# Volty.net
KiCad netlist of a schematic drawn in EAGLE
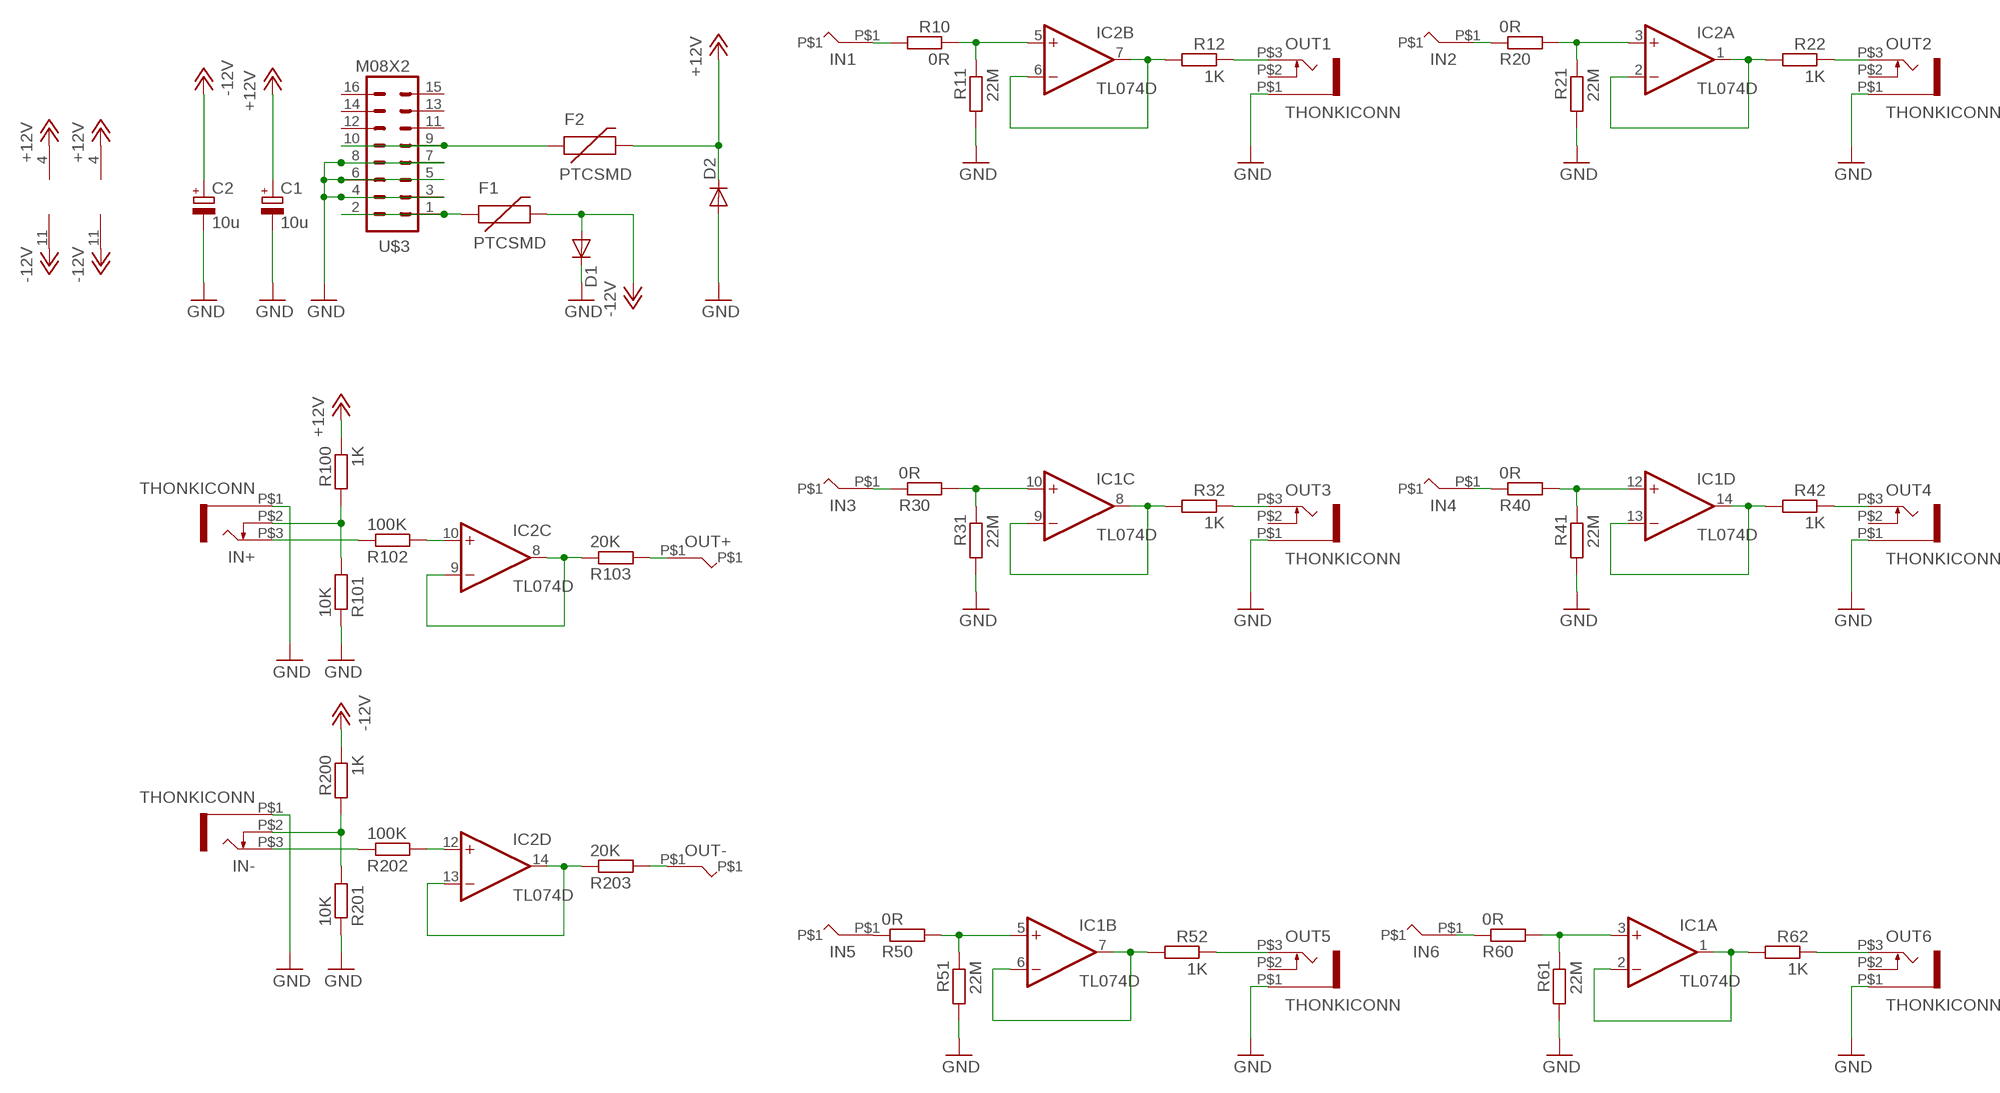
[diagram p0: schematic, sheet 1]

(export (version "E")
  (design (tool "Eeschema 10.0.6"))
  (components
    (comp (ref "C1")
      (value "10u")
      (footprint "eagle-import:E2,5-6")
      (libsource (lib "eagle-import") (part "CPOL-EUE2.5-6"))
    )
    (comp (ref "C2")
      (value "10u")
      (footprint "eagle-import:E2,5-6")
      (libsource (lib "eagle-import") (part "CPOL-EUE2.5-6"))
    )
    (comp (ref "D1")
      (value "DIODESMA")
      (footprint "eagle-import:SMA-DIODE")
      (libsource (lib "eagle-import") (part "DIODESMA"))
    )
    (comp (ref "D2")
      (value "DIODESMA")
      (footprint "eagle-import:SMA-DIODE")
      (libsource (lib "eagle-import") (part "DIODESMA"))
    )
    (comp (ref "F1")
      (value "PTCSMD")
      (footprint "eagle-import:PTC-1206")
      (libsource (lib "eagle-import") (part "PTCSMD"))
    )
    (comp (ref "F2")
      (value "PTCSMD")
      (footprint "eagle-import:PTC-1206")
      (libsource (lib "eagle-import") (part "PTCSMD"))
    )
    (comp (ref "IC1")
      (value "TL074D")
      (footprint "eagle-import:SO14")
      (libsource (lib "eagle-import") (part "TL074D"))
    )
    (comp (ref "IC2")
      (value "TL074D")
      (footprint "eagle-import:SO14")
      (libsource (lib "eagle-import") (part "TL074D"))
    )
    (comp (ref "IN+")
      (value "THONKICONN")
      (footprint "eagle-import:THONKICONN")
      (libsource (lib "eagle-import") (part "THONKICONN"))
    )
    (comp (ref "IN-")
      (value "THONKICONN")
      (footprint "eagle-import:THONKICONN")
      (libsource (lib "eagle-import") (part "THONKICONN"))
    )
    (comp (ref "IN1")
      (value "BANANAJACK")
      (footprint "eagle-import:BANANAJACK")
      (libsource (lib "eagle-import") (part "BANANAJACK"))
    )
    (comp (ref "IN2")
      (value "BANANAJACK")
      (footprint "eagle-import:BANANAJACK")
      (libsource (lib "eagle-import") (part "BANANAJACK"))
    )
    (comp (ref "IN3")
      (value "BANANAJACK")
      (footprint "eagle-import:BANANAJACK")
      (libsource (lib "eagle-import") (part "BANANAJACK"))
    )
    (comp (ref "IN4")
      (value "BANANAJACK")
      (footprint "eagle-import:BANANAJACK")
      (libsource (lib "eagle-import") (part "BANANAJACK"))
    )
    (comp (ref "IN5")
      (value "BANANAJACK")
      (footprint "eagle-import:BANANAJACK")
      (libsource (lib "eagle-import") (part "BANANAJACK"))
    )
    (comp (ref "IN6")
      (value "BANANAJACK")
      (footprint "eagle-import:BANANAJACK")
      (libsource (lib "eagle-import") (part "BANANAJACK"))
    )
    (comp (ref "OUT+")
      (value "BANANAJACK")
      (footprint "eagle-import:BANANAJACK")
      (libsource (lib "eagle-import") (part "BANANAJACK"))
    )
    (comp (ref "OUT-")
      (value "BANANAJACK")
      (footprint "eagle-import:BANANAJACK")
      (libsource (lib "eagle-import") (part "BANANAJACK"))
    )
    (comp (ref "OUT1")
      (value "THONKICONN")
      (footprint "eagle-import:THONKICONN")
      (libsource (lib "eagle-import") (part "THONKICONN"))
    )
    (comp (ref "OUT2")
      (value "THONKICONN")
      (footprint "eagle-import:THONKICONN")
      (libsource (lib "eagle-import") (part "THONKICONN"))
    )
    (comp (ref "OUT3")
      (value "THONKICONN")
      (footprint "eagle-import:THONKICONN")
      (libsource (lib "eagle-import") (part "THONKICONN"))
    )
    (comp (ref "OUT4")
      (value "THONKICONN")
      (footprint "eagle-import:THONKICONN")
      (libsource (lib "eagle-import") (part "THONKICONN"))
    )
    (comp (ref "OUT5")
      (value "THONKICONN")
      (footprint "eagle-import:THONKICONN")
      (libsource (lib "eagle-import") (part "THONKICONN"))
    )
    (comp (ref "OUT6")
      (value "THONKICONN")
      (footprint "eagle-import:THONKICONN")
      (libsource (lib "eagle-import") (part "THONKICONN"))
    )
    (comp (ref "R10")
      (value "0R")
      (footprint "eagle-import:0603")
      (libsource (lib "eagle-import") (part "R-EU_0603"))
    )
    (comp (ref "R11")
      (value "22M")
      (footprint "eagle-import:0603")
      (libsource (lib "eagle-import") (part "R-EU_0603"))
    )
    (comp (ref "R12")
      (value "1K")
      (footprint "eagle-import:0603")
      (libsource (lib "eagle-import") (part "R-EU_0603"))
    )
    (comp (ref "R20")
      (value "0R")
      (footprint "eagle-import:0603")
      (libsource (lib "eagle-import") (part "R-EU_0603"))
    )
    (comp (ref "R21")
      (value "22M")
      (footprint "eagle-import:0603")
      (libsource (lib "eagle-import") (part "R-EU_0603"))
    )
    (comp (ref "R22")
      (value "1K")
      (footprint "eagle-import:0603")
      (libsource (lib "eagle-import") (part "R-EU_0603"))
    )
    (comp (ref "R30")
      (value "0R")
      (footprint "eagle-import:0603")
      (libsource (lib "eagle-import") (part "R-EU_0603"))
    )
    (comp (ref "R31")
      (value "22M")
      (footprint "eagle-import:0603")
      (libsource (lib "eagle-import") (part "R-EU_0603"))
    )
    (comp (ref "R32")
      (value "1K")
      (footprint "eagle-import:0603")
      (libsource (lib "eagle-import") (part "R-EU_0603"))
    )
    (comp (ref "R40")
      (value "0R")
      (footprint "eagle-import:0603")
      (libsource (lib "eagle-import") (part "R-EU_0603"))
    )
    (comp (ref "R41")
      (value "22M")
      (footprint "eagle-import:0603")
      (libsource (lib "eagle-import") (part "R-EU_0603"))
    )
    (comp (ref "R42")
      (value "1K")
      (footprint "eagle-import:0603")
      (libsource (lib "eagle-import") (part "R-EU_0603"))
    )
    (comp (ref "R50")
      (value "0R")
      (footprint "eagle-import:0603")
      (libsource (lib "eagle-import") (part "R-EU_0603"))
    )
    (comp (ref "R51")
      (value "22M")
      (footprint "eagle-import:0603")
      (libsource (lib "eagle-import") (part "R-EU_0603"))
    )
    (comp (ref "R52")
      (value "1K")
      (footprint "eagle-import:0603")
      (libsource (lib "eagle-import") (part "R-EU_0603"))
    )
    (comp (ref "R60")
      (value "0R")
      (footprint "eagle-import:0603")
      (libsource (lib "eagle-import") (part "R-EU_0603"))
    )
    (comp (ref "R61")
      (value "22M")
      (footprint "eagle-import:0603")
      (libsource (lib "eagle-import") (part "R-EU_0603"))
    )
    (comp (ref "R62")
      (value "1K")
      (footprint "eagle-import:0603")
      (libsource (lib "eagle-import") (part "R-EU_0603"))
    )
    (comp (ref "R100")
      (value "1K")
      (footprint "eagle-import:0603")
      (libsource (lib "eagle-import") (part "R-EU_0603"))
    )
    (comp (ref "R101")
      (value "10K")
      (footprint "eagle-import:0603")
      (libsource (lib "eagle-import") (part "R-EU_0603"))
    )
    (comp (ref "R102")
      (value "100K")
      (footprint "eagle-import:0603")
      (libsource (lib "eagle-import") (part "R-EU_0603"))
    )
    (comp (ref "R103")
      (value "20K")
      (footprint "eagle-import:0603")
      (libsource (lib "eagle-import") (part "R-EU_0603"))
    )
    (comp (ref "R200")
      (value "1K")
      (footprint "eagle-import:0603")
      (libsource (lib "eagle-import") (part "R-EU_0603"))
    )
    (comp (ref "R201")
      (value "10K")
      (footprint "eagle-import:0603")
      (libsource (lib "eagle-import") (part "R-EU_0603"))
    )
    (comp (ref "R202")
      (value "100K")
      (footprint "eagle-import:0603")
      (libsource (lib "eagle-import") (part "R-EU_0603"))
    )
    (comp (ref "R203")
      (value "20K")
      (footprint "eagle-import:0603")
      (libsource (lib "eagle-import") (part "R-EU_0603"))
    )
    (comp (ref "U$3")
      (value "M08X2")
      (footprint "eagle-import:2X8")
      (libsource (lib "eagle-import") (part "M08X2"))
    )
  )
  (nets
    (net (code "1") (name "+12V") (class "Default")
      (node (ref "C1") (pin "+") (pinfunction "+_+") (pintype "passive"))
      (node (ref "D2") (pin "C") (pinfunction "C_C") (pintype "passive"))
      (node (ref "F2") (pin "2") (pinfunction "2_2") (pintype "bidirectional"))
      (node (ref "IC1") (pin "4") (pinfunction "V+_4") (pintype "power_in"))
      (node (ref "IC2") (pin "4") (pinfunction "V+_4") (pintype "power_in"))
      (node (ref "R100") (pin "1") (pinfunction "1_1") (pintype "passive"))
    )
    (net (code "2") (name "-12V") (class "Default")
      (node (ref "C2") (pin "+") (pinfunction "+_+") (pintype "passive"))
      (node (ref "D1") (pin "A") (pinfunction "A_A") (pintype "passive"))
      (node (ref "F1") (pin "2") (pinfunction "2_2") (pintype "bidirectional"))
      (node (ref "IC1") (pin "11") (pinfunction "V-_11") (pintype "power_in"))
      (node (ref "IC2") (pin "11") (pinfunction "V-_11") (pintype "power_in"))
      (node (ref "R200") (pin "1") (pinfunction "1_1") (pintype "passive"))
    )
    (net (code "3") (name "GND") (class "Default")
      (node (ref "C1") (pin "-") (pinfunction "-_-") (pintype "passive"))
      (node (ref "C2") (pin "-") (pinfunction "-_-") (pintype "passive"))
      (node (ref "D1") (pin "C") (pinfunction "C_C") (pintype "passive"))
      (node (ref "D2") (pin "A") (pinfunction "A_A") (pintype "passive"))
      (node (ref "IN+") (pin "P$1") (pinfunction "5_P$1") (pintype "passive"))
      (node (ref "IN-") (pin "P$1") (pinfunction "5_P$1") (pintype "passive"))
      (node (ref "OUT1") (pin "P$1") (pinfunction "5_P$1") (pintype "passive"))
      (node (ref "OUT2") (pin "P$1") (pinfunction "5_P$1") (pintype "passive"))
      (node (ref "OUT3") (pin "P$1") (pinfunction "5_P$1") (pintype "passive"))
      (node (ref "OUT4") (pin "P$1") (pinfunction "5_P$1") (pintype "passive"))
      (node (ref "OUT5") (pin "P$1") (pinfunction "5_P$1") (pintype "passive"))
      (node (ref "OUT6") (pin "P$1") (pinfunction "5_P$1") (pintype "passive"))
      (node (ref "R101") (pin "1") (pinfunction "1_1") (pintype "passive"))
      (node (ref "R11") (pin "2") (pinfunction "2_2") (pintype "passive"))
      (node (ref "R201") (pin "1") (pinfunction "1_1") (pintype "passive"))
      (node (ref "R21") (pin "2") (pinfunction "2_2") (pintype "passive"))
      (node (ref "R31") (pin "2") (pinfunction "2_2") (pintype "passive"))
      (node (ref "R41") (pin "2") (pinfunction "2_2") (pintype "passive"))
      (node (ref "R51") (pin "2") (pinfunction "2_2") (pintype "passive"))
      (node (ref "R61") (pin "2") (pinfunction "2_2") (pintype "passive"))
      (node (ref "U$3") (pin "3") (pinfunction "3_3") (pintype "passive"))
      (node (ref "U$3") (pin "4") (pinfunction "4_4") (pintype "passive"))
      (node (ref "U$3") (pin "5") (pinfunction "5_5") (pintype "passive"))
      (node (ref "U$3") (pin "6") (pinfunction "6_6") (pintype "passive"))
      (node (ref "U$3") (pin "7") (pinfunction "7_7") (pintype "passive"))
      (node (ref "U$3") (pin "8") (pinfunction "8_8") (pintype "passive"))
    )
    (net (code "4") (name "Net-(F1-Pad1)") (class "Default")
      (node (ref "F1") (pin "1") (pinfunction "1_1") (pintype "bidirectional"))
      (node (ref "U$3") (pin "1") (pinfunction "1_1") (pintype "passive"))
      (node (ref "U$3") (pin "2") (pinfunction "2_2") (pintype "passive"))
    )
    (net (code "5") (name "Net-(F2-Pad1)") (class "Default")
      (node (ref "F2") (pin "1") (pinfunction "1_1") (pintype "bidirectional"))
      (node (ref "U$3") (pin "10") (pinfunction "10_10") (pintype "passive"))
      (node (ref "U$3") (pin "9") (pinfunction "9_9") (pintype "passive"))
    )
    (net (code "6") (name "Net-(IC1A-+IN)") (class "Default")
      (node (ref "IC1") (pin "3") (pinfunction "+IN_3") (pintype "input"))
      (node (ref "R60") (pin "2") (pinfunction "2_2") (pintype "passive"))
      (node (ref "R61") (pin "1") (pinfunction "1_1") (pintype "passive"))
    )
    (net (code "7") (name "Net-(IC1A--IN)") (class "Default")
      (node (ref "IC1") (pin "1") (pinfunction "OUT_1") (pintype "output"))
      (node (ref "IC1") (pin "2") (pinfunction "-IN_2") (pintype "input"))
      (node (ref "R62") (pin "2") (pinfunction "2_2") (pintype "passive"))
    )
    (net (code "8") (name "Net-(IC1B-+IN)") (class "Default")
      (node (ref "IC1") (pin "5") (pinfunction "+IN_5") (pintype "input"))
      (node (ref "R50") (pin "2") (pinfunction "2_2") (pintype "passive"))
      (node (ref "R51") (pin "1") (pinfunction "1_1") (pintype "passive"))
    )
    (net (code "9") (name "Net-(IC1B--IN)") (class "Default")
      (node (ref "IC1") (pin "6") (pinfunction "-IN_6") (pintype "input"))
      (node (ref "IC1") (pin "7") (pinfunction "OUT_7") (pintype "output"))
      (node (ref "R52") (pin "2") (pinfunction "2_2") (pintype "passive"))
    )
    (net (code "10") (name "Net-(IC1C-+IN)") (class "Default")
      (node (ref "IC1") (pin "10") (pinfunction "+IN_10") (pintype "input"))
      (node (ref "R30") (pin "2") (pinfunction "2_2") (pintype "passive"))
      (node (ref "R31") (pin "1") (pinfunction "1_1") (pintype "passive"))
    )
    (net (code "11") (name "Net-(IC1C--IN)") (class "Default")
      (node (ref "IC1") (pin "8") (pinfunction "OUT_8") (pintype "output"))
      (node (ref "IC1") (pin "9") (pinfunction "-IN_9") (pintype "input"))
      (node (ref "R32") (pin "2") (pinfunction "2_2") (pintype "passive"))
    )
    (net (code "12") (name "Net-(IC1D-+IN)") (class "Default")
      (node (ref "IC1") (pin "12") (pinfunction "+IN_12") (pintype "input"))
      (node (ref "R40") (pin "2") (pinfunction "2_2") (pintype "passive"))
      (node (ref "R41") (pin "1") (pinfunction "1_1") (pintype "passive"))
    )
    (net (code "13") (name "Net-(IC1D--IN)") (class "Default")
      (node (ref "IC1") (pin "13") (pinfunction "-IN_13") (pintype "input"))
      (node (ref "IC1") (pin "14") (pinfunction "OUT_14") (pintype "output"))
      (node (ref "R42") (pin "2") (pinfunction "2_2") (pintype "passive"))
    )
    (net (code "14") (name "Net-(IC2A-+IN)") (class "Default")
      (node (ref "IC2") (pin "3") (pinfunction "+IN_3") (pintype "input"))
      (node (ref "R20") (pin "2") (pinfunction "2_2") (pintype "passive"))
      (node (ref "R21") (pin "1") (pinfunction "1_1") (pintype "passive"))
    )
    (net (code "15") (name "Net-(IC2A--IN)") (class "Default")
      (node (ref "IC2") (pin "1") (pinfunction "OUT_1") (pintype "output"))
      (node (ref "IC2") (pin "2") (pinfunction "-IN_2") (pintype "input"))
      (node (ref "R22") (pin "2") (pinfunction "2_2") (pintype "passive"))
    )
    (net (code "16") (name "Net-(IC2B-+IN)") (class "Default")
      (node (ref "IC2") (pin "5") (pinfunction "+IN_5") (pintype "input"))
      (node (ref "R10") (pin "1") (pinfunction "1_1") (pintype "passive"))
      (node (ref "R11") (pin "1") (pinfunction "1_1") (pintype "passive"))
    )
    (net (code "17") (name "Net-(IC2B--IN)") (class "Default")
      (node (ref "IC2") (pin "6") (pinfunction "-IN_6") (pintype "input"))
      (node (ref "IC2") (pin "7") (pinfunction "OUT_7") (pintype "output"))
      (node (ref "R12") (pin "2") (pinfunction "2_2") (pintype "passive"))
    )
    (net (code "18") (name "Net-(IC2C-+IN)") (class "Default")
      (node (ref "IC2") (pin "10") (pinfunction "+IN_10") (pintype "input"))
      (node (ref "R102") (pin "2") (pinfunction "2_2") (pintype "passive"))
    )
    (net (code "19") (name "Net-(IC2C--IN)") (class "Default")
      (node (ref "IC2") (pin "8") (pinfunction "OUT_8") (pintype "output"))
      (node (ref "IC2") (pin "9") (pinfunction "-IN_9") (pintype "input"))
      (node (ref "R103") (pin "1") (pinfunction "1_1") (pintype "passive"))
    )
    (net (code "20") (name "Net-(IC2D-+IN)") (class "Default")
      (node (ref "IC2") (pin "12") (pinfunction "+IN_12") (pintype "input"))
      (node (ref "R202") (pin "2") (pinfunction "2_2") (pintype "passive"))
    )
    (net (code "21") (name "Net-(IC2D--IN)") (class "Default")
      (node (ref "IC2") (pin "13") (pinfunction "-IN_13") (pintype "input"))
      (node (ref "IC2") (pin "14") (pinfunction "OUT_14") (pintype "output"))
      (node (ref "R203") (pin "1") (pinfunction "1_1") (pintype "passive"))
    )
    (net (code "22") (name "Net-(IN+-3)") (class "Default")
      (node (ref "IN+") (pin "P$3") (pinfunction "3_P$3") (pintype "passive"))
      (node (ref "R102") (pin "1") (pinfunction "1_1") (pintype "passive"))
    )
    (net (code "23") (name "Net-(IN+-4)") (class "Default")
      (node (ref "IN+") (pin "P$2") (pinfunction "4_P$2") (pintype "passive"))
      (node (ref "R100") (pin "2") (pinfunction "2_2") (pintype "passive"))
      (node (ref "R101") (pin "2") (pinfunction "2_2") (pintype "passive"))
    )
    (net (code "24") (name "Net-(IN--3)") (class "Default")
      (node (ref "IN-") (pin "P$3") (pinfunction "3_P$3") (pintype "passive"))
      (node (ref "R202") (pin "1") (pinfunction "1_1") (pintype "passive"))
    )
    (net (code "25") (name "Net-(IN--4)") (class "Default")
      (node (ref "IN-") (pin "P$2") (pinfunction "4_P$2") (pintype "passive"))
      (node (ref "R200") (pin "2") (pinfunction "2_2") (pintype "passive"))
      (node (ref "R201") (pin "2") (pinfunction "2_2") (pintype "passive"))
    )
    (net (code "26") (name "Net-(IN1-PadP$1)") (class "Default")
      (node (ref "IN1") (pin "P$1") (pinfunction "P$1_P$1") (pintype "bidirectional"))
      (node (ref "R10") (pin "2") (pinfunction "2_2") (pintype "passive"))
    )
    (net (code "27") (name "Net-(IN2-PadP$1)") (class "Default")
      (node (ref "IN2") (pin "P$1") (pinfunction "P$1_P$1") (pintype "bidirectional"))
      (node (ref "R20") (pin "1") (pinfunction "1_1") (pintype "passive"))
    )
    (net (code "28") (name "Net-(IN3-PadP$1)") (class "Default")
      (node (ref "IN3") (pin "P$1") (pinfunction "P$1_P$1") (pintype "bidirectional"))
      (node (ref "R30") (pin "1") (pinfunction "1_1") (pintype "passive"))
    )
    (net (code "29") (name "Net-(IN4-PadP$1)") (class "Default")
      (node (ref "IN4") (pin "P$1") (pinfunction "P$1_P$1") (pintype "bidirectional"))
      (node (ref "R40") (pin "1") (pinfunction "1_1") (pintype "passive"))
    )
    (net (code "30") (name "Net-(IN5-PadP$1)") (class "Default")
      (node (ref "IN5") (pin "P$1") (pinfunction "P$1_P$1") (pintype "bidirectional"))
      (node (ref "R50") (pin "1") (pinfunction "1_1") (pintype "passive"))
    )
    (net (code "31") (name "Net-(IN6-PadP$1)") (class "Default")
      (node (ref "IN6") (pin "P$1") (pinfunction "P$1_P$1") (pintype "bidirectional"))
      (node (ref "R60") (pin "1") (pinfunction "1_1") (pintype "passive"))
    )
    (net (code "32") (name "Net-(OUT+-PadP$1)") (class "Default")
      (node (ref "OUT+") (pin "P$1") (pinfunction "P$1_P$1") (pintype "bidirectional"))
      (node (ref "R103") (pin "2") (pinfunction "2_2") (pintype "passive"))
    )
    (net (code "33") (name "Net-(OUT--PadP$1)") (class "Default")
      (node (ref "OUT-") (pin "P$1") (pinfunction "P$1_P$1") (pintype "bidirectional"))
      (node (ref "R203") (pin "2") (pinfunction "2_2") (pintype "passive"))
    )
    (net (code "34") (name "Net-(OUT1-3)") (class "Default")
      (node (ref "OUT1") (pin "P$3") (pinfunction "3_P$3") (pintype "passive"))
      (node (ref "R12") (pin "1") (pinfunction "1_1") (pintype "passive"))
    )
    (net (code "35") (name "Net-(OUT2-3)") (class "Default")
      (node (ref "OUT2") (pin "P$3") (pinfunction "3_P$3") (pintype "passive"))
      (node (ref "R22") (pin "1") (pinfunction "1_1") (pintype "passive"))
    )
    (net (code "36") (name "Net-(OUT3-3)") (class "Default")
      (node (ref "OUT3") (pin "P$3") (pinfunction "3_P$3") (pintype "passive"))
      (node (ref "R32") (pin "1") (pinfunction "1_1") (pintype "passive"))
    )
    (net (code "37") (name "Net-(OUT4-3)") (class "Default")
      (node (ref "OUT4") (pin "P$3") (pinfunction "3_P$3") (pintype "passive"))
      (node (ref "R42") (pin "1") (pinfunction "1_1") (pintype "passive"))
    )
    (net (code "38") (name "Net-(OUT5-3)") (class "Default")
      (node (ref "OUT5") (pin "P$3") (pinfunction "3_P$3") (pintype "passive"))
      (node (ref "R52") (pin "1") (pinfunction "1_1") (pintype "passive"))
    )
    (net (code "39") (name "Net-(OUT6-3)") (class "Default")
      (node (ref "OUT6") (pin "P$3") (pinfunction "3_P$3") (pintype "passive"))
      (node (ref "R62") (pin "1") (pinfunction "1_1") (pintype "passive"))
    )
    (net (code "40") (name "unconnected-(OUT1-4-PadP$2)") (class "Default")
      (node (ref "OUT1") (pin "P$2") (pinfunction "4_P$2") (pintype "passive"))
    )
    (net (code "41") (name "unconnected-(OUT2-4-PadP$2)") (class "Default")
      (node (ref "OUT2") (pin "P$2") (pinfunction "4_P$2") (pintype "passive"))
    )
    (net (code "42") (name "unconnected-(OUT3-4-PadP$2)") (class "Default")
      (node (ref "OUT3") (pin "P$2") (pinfunction "4_P$2") (pintype "passive"))
    )
    (net (code "43") (name "unconnected-(OUT4-4-PadP$2)") (class "Default")
      (node (ref "OUT4") (pin "P$2") (pinfunction "4_P$2") (pintype "passive"))
    )
    (net (code "44") (name "unconnected-(OUT5-4-PadP$2)") (class "Default")
      (node (ref "OUT5") (pin "P$2") (pinfunction "4_P$2") (pintype "passive"))
    )
    (net (code "45") (name "unconnected-(OUT6-4-PadP$2)") (class "Default")
      (node (ref "OUT6") (pin "P$2") (pinfunction "4_P$2") (pintype "passive"))
    )
    (net (code "46") (name "unconnected-(U$3-Pad11)") (class "Default")
      (node (ref "U$3") (pin "11") (pinfunction "11_11") (pintype "passive"))
    )
    (net (code "47") (name "unconnected-(U$3-Pad12)") (class "Default")
      (node (ref "U$3") (pin "12") (pinfunction "12_12") (pintype "passive"))
    )
    (net (code "48") (name "unconnected-(U$3-Pad13)") (class "Default")
      (node (ref "U$3") (pin "13") (pinfunction "13_13") (pintype "passive"))
    )
    (net (code "49") (name "unconnected-(U$3-Pad14)") (class "Default")
      (node (ref "U$3") (pin "14") (pinfunction "14_14") (pintype "passive"))
    )
    (net (code "50") (name "unconnected-(U$3-Pad15)") (class "Default")
      (node (ref "U$3") (pin "15") (pinfunction "15_15") (pintype "passive"))
    )
    (net (code "51") (name "unconnected-(U$3-Pad16)") (class "Default")
      (node (ref "U$3") (pin "16") (pinfunction "16_16") (pintype "passive"))
    )
  )
)
